# Control.net
KiCad netlist of a schematic drawn in Altium Designer
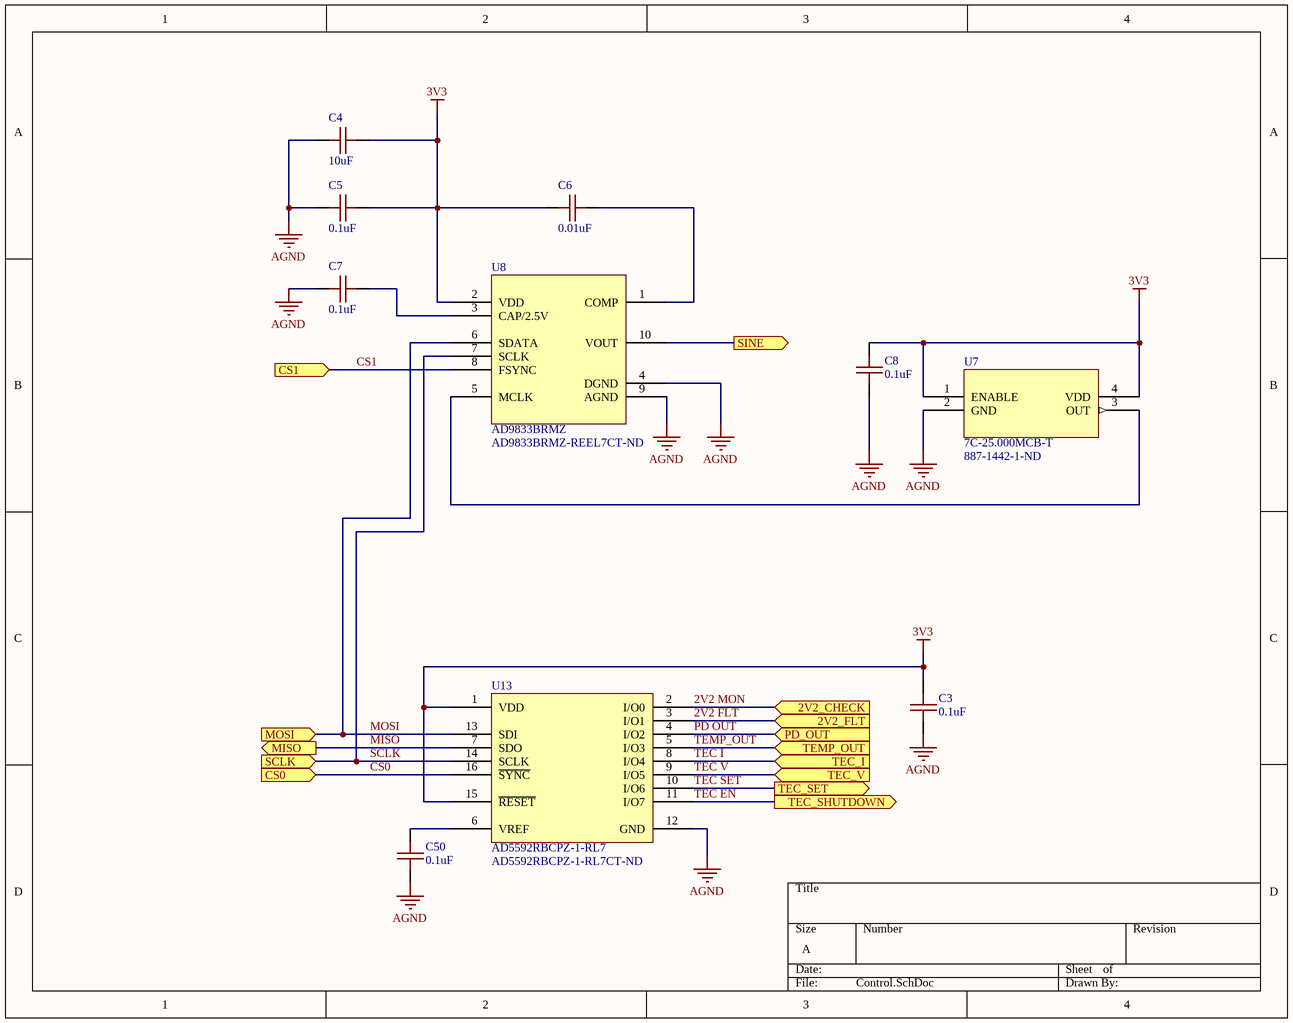
[diagram p0: Control.SchDoc]

(export (version "E")
  (design (tool "Eeschema 10.0.6"))
  (components
    (comp (ref "C3")
      (value "0.1uF")
      (footprint "0603 B")
      (description "603 Capacitor")
      (libsource (lib "PSSL3") (part "CAP 0603"))
    )
    (comp (ref "C4")
      (value "10uF")
      (footprint "0603 B")
      (description "603 Capacitor")
      (libsource (lib "PSSL3") (part "CAP 0603"))
    )
    (comp (ref "C5")
      (value "0.1uF")
      (footprint "0603 B")
      (description "603 Capacitor")
      (libsource (lib "PSSL3") (part "CAP 0603"))
    )
    (comp (ref "C6")
      (value "0.01uF")
      (footprint "0603 B")
      (description "603 Capacitor")
      (libsource (lib "PSSL3") (part "CAP 0603"))
    )
    (comp (ref "C7")
      (value "0.1uF")
      (footprint "0603 B")
      (description "603 Capacitor")
      (libsource (lib "PSSL3") (part "CAP 0603"))
    )
    (comp (ref "C8")
      (value "0.1uF")
      (footprint "0603 B")
      (description "603 Capacitor")
      (libsource (lib "PSSL3") (part "CAP 0603"))
    )
    (comp (ref "C50")
      (value "0.1uF")
      (footprint "0603 B")
      (description "603 Capacitor")
      (libsource (lib "PSSL3") (part "CAP 0603"))
    )
    (comp (ref "U7")
      (value "7C-25.000MCB-T")
      (footprint "OSC_TXC_7C_TXC")
      (description "25 MHz XO (Standard) CMOS Oscillator 2.5V Enable/Disable 4-SMD, No Lead")
      (fields
        (field (name "SUPPLIER PART NUMBER 1") "887-1442-1-ND")
        (field (name "COPYRIGHT") "Copyright (C) 2021 Accelerated Designs. All rights reserved")
      )
      (libsource (lib "BeaconBoard") (part "7C-25.000MCB-T"))
    )
    (comp (ref "U8")
      (value "AD9833BRMZ")
      (footprint "RM_10_ADI")
      (description "Low Power, 12.65 mW, 2.3 V to 5.5 V, Programmable Waveform Generator")
      (fields
        (field (name "SUPPLIER PART NUMBER 1") "AD9833BRMZ-REEL7CT-ND")
        (field (name "COPYRIGHT") "Copyright (C) 2018 Accelerated Designs. All rights reserved")
      )
      (libsource (lib "BeaconBoard") (part "AD9833BRMZ"))
    )
    (comp (ref "U13")
      (value "AD5592RBCPZ-1-RL7")
      (footprint "LFCSP CP 16 2")
      (description "8-Channel, 12-Bit, Configurable ADC/DAC with On-Chip Reference, SPI Interface, LFCSP")
      (fields
        (field (name "SUPPLIER PART NUMBER 1") "AD5592RBCPZ-1-RL7CT-ND")
        (field (name "COPYRIGHT") "Copyright (C) 2021 Accelerated Designs. All rights reserved")
      )
      (libsource (lib "BeaconBoard") (part "AD5592RBCPZ-1-RL7"))
    )
  )
  (nets
    (net (code "1") (name "/2V2 FLT") (class "Default")
      (node (ref "U13") (pin "3") (pinfunction "I/O1_3") (pintype "passive"))
    )
    (net (code "2") (name "/2V2 MON") (class "Default")
      (node (ref "U13") (pin "2") (pinfunction "I/O0_2") (pintype "passive"))
    )
    (net (code "3") (name "/CS0") (class "Default")
      (node (ref "U13") (pin "16") (pinfunction "~{SYNC}_16") (pintype "passive"))
    )
    (net (code "4") (name "/CS1") (class "Default")
      (node (ref "U8") (pin "8") (pinfunction "FSYNC_8") (pintype "passive"))
    )
    (net (code "5") (name "/MISO") (class "Default")
      (node (ref "U13") (pin "7") (pinfunction "SDO_7") (pintype "passive"))
    )
    (net (code "6") (name "/MOSI") (class "Default")
      (node (ref "U13") (pin "13") (pinfunction "SDI_13") (pintype "passive"))
      (node (ref "U8") (pin "6") (pinfunction "SDATA_6") (pintype "passive"))
    )
    (net (code "7") (name "/PD OUT") (class "Default")
      (node (ref "U13") (pin "4") (pinfunction "I/O2_4") (pintype "passive"))
    )
    (net (code "8") (name "/SCLK") (class "Default")
      (node (ref "U13") (pin "14") (pinfunction "SCLK_14") (pintype "passive"))
      (node (ref "U8") (pin "7") (pinfunction "SCLK_7") (pintype "passive"))
    )
    (net (code "9") (name "/SINE") (class "Default")
      (node (ref "U8") (pin "10") (pinfunction "VOUT_10") (pintype "passive"))
    )
    (net (code "10") (name "/TEC EN") (class "Default")
      (node (ref "U13") (pin "11") (pinfunction "I/O7_11") (pintype "passive"))
    )
    (net (code "11") (name "/TEC I") (class "Default")
      (node (ref "U13") (pin "8") (pinfunction "I/O4_8") (pintype "passive"))
    )
    (net (code "12") (name "/TEC SET") (class "Default")
      (node (ref "U13") (pin "10") (pinfunction "I/O6_10") (pintype "passive"))
    )
    (net (code "13") (name "/TEC V") (class "Default")
      (node (ref "U13") (pin "9") (pinfunction "I/O5_9") (pintype "passive"))
    )
    (net (code "14") (name "/TEMP_OUT") (class "Default")
      (node (ref "U13") (pin "5") (pinfunction "I/O3_5") (pintype "passive"))
    )
    (net (code "15") (name "3V3") (class "Default")
      (node (ref "C3") (pin "1") (pintype "passive"))
      (node (ref "C4") (pin "2") (pintype "passive"))
      (node (ref "C5") (pin "2") (pintype "passive"))
      (node (ref "C6") (pin "1") (pintype "passive"))
      (node (ref "C8") (pin "2") (pintype "passive"))
      (node (ref "U13") (pin "1") (pinfunction "VDD_1") (pintype "passive"))
      (node (ref "U13") (pin "15") (pinfunction "~{RESET}_15") (pintype "passive"))
      (node (ref "U7") (pin "1") (pinfunction "ENABLE_1") (pintype "passive"))
      (node (ref "U7") (pin "4") (pinfunction "VDD_4") (pintype "power_in"))
      (node (ref "U8") (pin "2") (pinfunction "VDD_2") (pintype "power_in"))
    )
    (net (code "16") (name "AGND") (class "Default")
      (node (ref "C3") (pin "2") (pintype "passive"))
      (node (ref "C4") (pin "1") (pintype "passive"))
      (node (ref "C5") (pin "1") (pintype "passive"))
      (node (ref "C50") (pin "1") (pintype "passive"))
      (node (ref "C7") (pin "1") (pintype "passive"))
      (node (ref "C8") (pin "1") (pintype "passive"))
      (node (ref "U13") (pin "12") (pinfunction "GND_12") (pintype "passive"))
      (node (ref "U7") (pin "2") (pinfunction "GND_2") (pintype "power_in"))
      (node (ref "U8") (pin "4") (pinfunction "DGND_4") (pintype "passive"))
      (node (ref "U8") (pin "9") (pinfunction "AGND_9") (pintype "passive"))
    )
    (net (code "17") (name "Net-(U7-OUT)") (class "Default")
      (node (ref "U7") (pin "3") (pinfunction "OUT_3") (pintype "output"))
      (node (ref "U8") (pin "5") (pinfunction "MCLK_5") (pintype "passive"))
    )
    (net (code "18") (name "Net-(U8-CAP{slash}2.5V)") (class "Default")
      (node (ref "C7") (pin "2") (pintype "passive"))
      (node (ref "U8") (pin "3") (pinfunction "CAP/2.5V_3") (pintype "power_in"))
    )
    (net (code "19") (name "Net-(U8-COMP)") (class "Default")
      (node (ref "C6") (pin "2") (pintype "passive"))
      (node (ref "U8") (pin "1") (pinfunction "COMP_1") (pintype "passive"))
    )
    (net (code "20") (name "Net-(U13-VREF)") (class "Default")
      (node (ref "C50") (pin "2") (pintype "passive"))
      (node (ref "U13") (pin "6") (pinfunction "VREF_6") (pintype "passive"))
    )
  )
)
